# quad_exp_vca_main.net
KiCad netlist of a schematic drawn in EAGLE
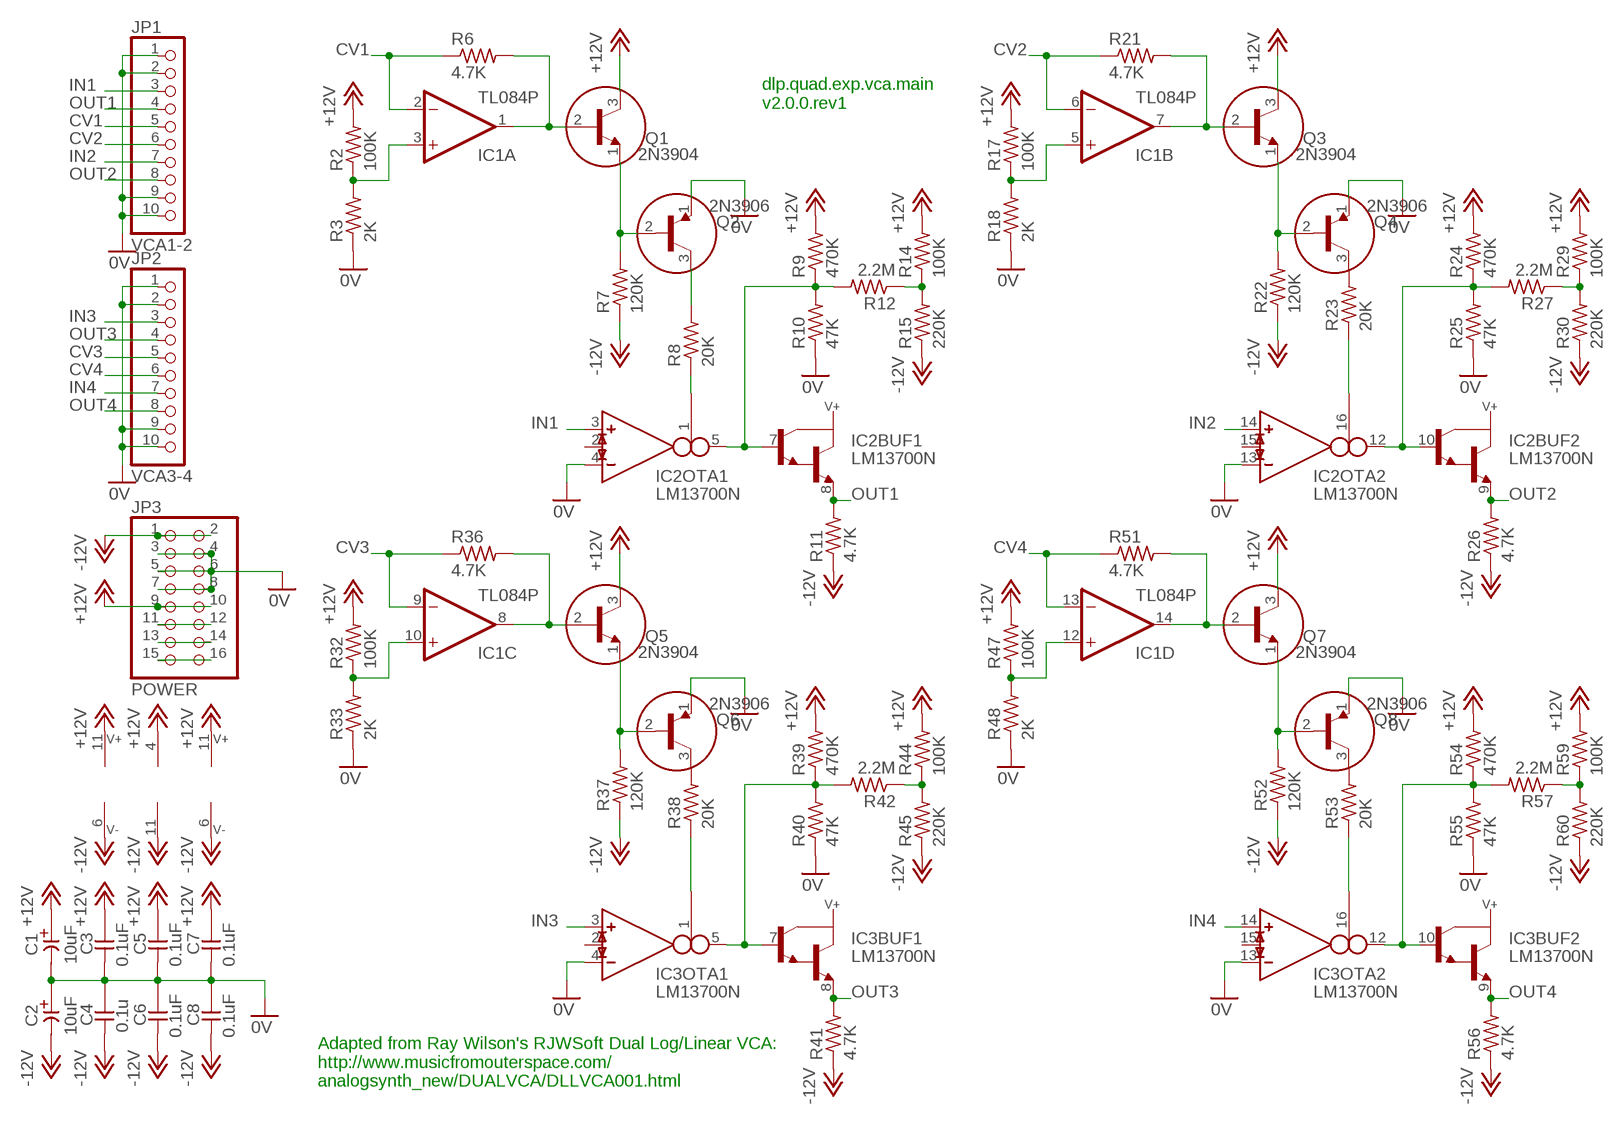
[diagram p0: schematic, sheet 1]

(export (version "E")
  (design (tool "Eeschema 10.0.6"))
  (components
    (comp (ref "C1")
      (value "10uF")
      (footprint "eagle-import:E2-5")
      (libsource (lib "eagle-import") (part "CE-USE2-5"))
    )
    (comp (ref "C2")
      (value "10uF")
      (footprint "eagle-import:E2-5")
      (libsource (lib "eagle-import") (part "CE-USE2-5"))
    )
    (comp (ref "C3")
      (value "0.1uF")
      (footprint "eagle-import:C025-024X044")
      (libsource (lib "eagle-import") (part "CC-US025-024X044"))
    )
    (comp (ref "C4")
      (value "0.1u")
      (footprint "eagle-import:C025-024X044")
      (libsource (lib "eagle-import") (part "CC-US025-024X044"))
    )
    (comp (ref "C5")
      (value "0.1uF")
      (footprint "eagle-import:C025-024X044")
      (libsource (lib "eagle-import") (part "CC-US025-024X044"))
    )
    (comp (ref "C6")
      (value "0.1uF")
      (footprint "eagle-import:C025-024X044")
      (libsource (lib "eagle-import") (part "CC-US025-024X044"))
    )
    (comp (ref "C7")
      (value "0.1uF")
      (footprint "eagle-import:C025-024X044")
      (libsource (lib "eagle-import") (part "CC-US025-024X044"))
    )
    (comp (ref "C8")
      (value "0.1uF")
      (footprint "eagle-import:C025-024X044")
      (libsource (lib "eagle-import") (part "CC-US025-024X044"))
    )
    (comp (ref "IC1")
      (value "TL084P")
      (footprint "eagle-import:DIL14")
      (libsource (lib "eagle-import") (part "TL084P"))
    )
    (comp (ref "IC2")
      (value "LM13700N")
      (footprint "eagle-import:DIL16")
      (libsource (lib "eagle-import") (part "LM13700N"))
    )
    (comp (ref "IC3")
      (value "LM13700N")
      (footprint "eagle-import:DIL16")
      (libsource (lib "eagle-import") (part "LM13700N"))
    )
    (comp (ref "JP1")
      (value "VCA1-2")
      (footprint "eagle-import:1X10")
      (libsource (lib "eagle-import") (part "PINHD-1X10"))
    )
    (comp (ref "JP2")
      (value "VCA3-4")
      (footprint "eagle-import:1X10")
      (libsource (lib "eagle-import") (part "PINHD-1X10"))
    )
    (comp (ref "JP3")
      (value "POWER")
      (footprint "eagle-import:2X08")
      (libsource (lib "eagle-import") (part "PINHD-2X8"))
    )
    (comp (ref "Q1")
      (value "2N3904")
      (footprint "eagle-import:TO92")
      (libsource (lib "eagle-import") (part "2N3904"))
    )
    (comp (ref "Q2")
      (value "2N3906")
      (footprint "eagle-import:TO92")
      (libsource (lib "eagle-import") (part "2N3906"))
    )
    (comp (ref "Q3")
      (value "2N3904")
      (footprint "eagle-import:TO92")
      (libsource (lib "eagle-import") (part "2N3904"))
    )
    (comp (ref "Q4")
      (value "2N3906")
      (footprint "eagle-import:TO92")
      (libsource (lib "eagle-import") (part "2N3906"))
    )
    (comp (ref "Q5")
      (value "2N3904")
      (footprint "eagle-import:TO92")
      (libsource (lib "eagle-import") (part "2N3904"))
    )
    (comp (ref "Q6")
      (value "2N3906")
      (footprint "eagle-import:TO92")
      (libsource (lib "eagle-import") (part "2N3906"))
    )
    (comp (ref "Q7")
      (value "2N3904")
      (footprint "eagle-import:TO92")
      (libsource (lib "eagle-import") (part "2N3904"))
    )
    (comp (ref "Q8")
      (value "2N3906")
      (footprint "eagle-import:TO92")
      (libsource (lib "eagle-import") (part "2N3906"))
    )
    (comp (ref "R2")
      (value "100K")
      (footprint "eagle-import:0207_7")
      (libsource (lib "eagle-import") (part "R-US_0207/7"))
    )
    (comp (ref "R3")
      (value "2K")
      (footprint "eagle-import:0207_7")
      (libsource (lib "eagle-import") (part "R-US_0207/7"))
    )
    (comp (ref "R6")
      (value "4.7K")
      (footprint "eagle-import:0207_7")
      (libsource (lib "eagle-import") (part "R-US_0207/7"))
    )
    (comp (ref "R7")
      (value "120K")
      (footprint "eagle-import:0207_7")
      (libsource (lib "eagle-import") (part "R-US_0207/7"))
    )
    (comp (ref "R8")
      (value "20K")
      (footprint "eagle-import:0207_7")
      (libsource (lib "eagle-import") (part "R-US_0207/7"))
    )
    (comp (ref "R9")
      (value "470K")
      (footprint "eagle-import:0207_7")
      (libsource (lib "eagle-import") (part "R-US_0207/7"))
    )
    (comp (ref "R10")
      (value "47K")
      (footprint "eagle-import:0207_7")
      (libsource (lib "eagle-import") (part "R-US_0207/7"))
    )
    (comp (ref "R11")
      (value "4.7K")
      (footprint "eagle-import:0207_7")
      (libsource (lib "eagle-import") (part "R-US_0207/7"))
    )
    (comp (ref "R12")
      (value "2.2M")
      (footprint "eagle-import:0207_7")
      (libsource (lib "eagle-import") (part "R-US_0207/7"))
    )
    (comp (ref "R14")
      (value "100K")
      (footprint "eagle-import:0207_7")
      (libsource (lib "eagle-import") (part "R-US_0207/7"))
    )
    (comp (ref "R15")
      (value "220K")
      (footprint "eagle-import:0207_7")
      (libsource (lib "eagle-import") (part "R-US_0207/7"))
    )
    (comp (ref "R17")
      (value "100K")
      (footprint "eagle-import:0207_7")
      (libsource (lib "eagle-import") (part "R-US_0207/7"))
    )
    (comp (ref "R18")
      (value "2K")
      (footprint "eagle-import:0207_7")
      (libsource (lib "eagle-import") (part "R-US_0207/7"))
    )
    (comp (ref "R21")
      (value "4.7K")
      (footprint "eagle-import:0207_7")
      (libsource (lib "eagle-import") (part "R-US_0207/7"))
    )
    (comp (ref "R22")
      (value "120K")
      (footprint "eagle-import:0207_7")
      (libsource (lib "eagle-import") (part "R-US_0207/7"))
    )
    (comp (ref "R23")
      (value "20K")
      (footprint "eagle-import:0207_7")
      (libsource (lib "eagle-import") (part "R-US_0207/7"))
    )
    (comp (ref "R24")
      (value "470K")
      (footprint "eagle-import:0207_7")
      (libsource (lib "eagle-import") (part "R-US_0207/7"))
    )
    (comp (ref "R25")
      (value "47K")
      (footprint "eagle-import:0207_7")
      (libsource (lib "eagle-import") (part "R-US_0207/7"))
    )
    (comp (ref "R26")
      (value "4.7K")
      (footprint "eagle-import:0207_7")
      (libsource (lib "eagle-import") (part "R-US_0207/7"))
    )
    (comp (ref "R27")
      (value "2.2M")
      (footprint "eagle-import:0207_7")
      (libsource (lib "eagle-import") (part "R-US_0207/7"))
    )
    (comp (ref "R29")
      (value "100K")
      (footprint "eagle-import:0207_7")
      (libsource (lib "eagle-import") (part "R-US_0207/7"))
    )
    (comp (ref "R30")
      (value "220K")
      (footprint "eagle-import:0207_7")
      (libsource (lib "eagle-import") (part "R-US_0207/7"))
    )
    (comp (ref "R32")
      (value "100K")
      (footprint "eagle-import:0207_7")
      (libsource (lib "eagle-import") (part "R-US_0207/7"))
    )
    (comp (ref "R33")
      (value "2K")
      (footprint "eagle-import:0207_7")
      (libsource (lib "eagle-import") (part "R-US_0207/7"))
    )
    (comp (ref "R36")
      (value "4.7K")
      (footprint "eagle-import:0207_7")
      (libsource (lib "eagle-import") (part "R-US_0207/7"))
    )
    (comp (ref "R37")
      (value "120K")
      (footprint "eagle-import:0207_7")
      (libsource (lib "eagle-import") (part "R-US_0207/7"))
    )
    (comp (ref "R38")
      (value "20K")
      (footprint "eagle-import:0207_7")
      (libsource (lib "eagle-import") (part "R-US_0207/7"))
    )
    (comp (ref "R39")
      (value "470K")
      (footprint "eagle-import:0207_7")
      (libsource (lib "eagle-import") (part "R-US_0207/7"))
    )
    (comp (ref "R40")
      (value "47K")
      (footprint "eagle-import:0207_7")
      (libsource (lib "eagle-import") (part "R-US_0207/7"))
    )
    (comp (ref "R41")
      (value "4.7K")
      (footprint "eagle-import:0207_7")
      (libsource (lib "eagle-import") (part "R-US_0207/7"))
    )
    (comp (ref "R42")
      (value "2.2M")
      (footprint "eagle-import:0207_7")
      (libsource (lib "eagle-import") (part "R-US_0207/7"))
    )
    (comp (ref "R44")
      (value "100K")
      (footprint "eagle-import:0207_7")
      (libsource (lib "eagle-import") (part "R-US_0207/7"))
    )
    (comp (ref "R45")
      (value "220K")
      (footprint "eagle-import:0207_7")
      (libsource (lib "eagle-import") (part "R-US_0207/7"))
    )
    (comp (ref "R47")
      (value "100K")
      (footprint "eagle-import:0207_7")
      (libsource (lib "eagle-import") (part "R-US_0207/7"))
    )
    (comp (ref "R48")
      (value "2K")
      (footprint "eagle-import:0207_7")
      (libsource (lib "eagle-import") (part "R-US_0207/7"))
    )
    (comp (ref "R51")
      (value "4.7K")
      (footprint "eagle-import:0207_7")
      (libsource (lib "eagle-import") (part "R-US_0207/7"))
    )
    (comp (ref "R52")
      (value "120K")
      (footprint "eagle-import:0207_7")
      (libsource (lib "eagle-import") (part "R-US_0207/7"))
    )
    (comp (ref "R53")
      (value "20K")
      (footprint "eagle-import:0207_7")
      (libsource (lib "eagle-import") (part "R-US_0207/7"))
    )
    (comp (ref "R54")
      (value "470K")
      (footprint "eagle-import:0207_7")
      (libsource (lib "eagle-import") (part "R-US_0207/7"))
    )
    (comp (ref "R55")
      (value "47K")
      (footprint "eagle-import:0207_7")
      (libsource (lib "eagle-import") (part "R-US_0207/7"))
    )
    (comp (ref "R56")
      (value "4.7K")
      (footprint "eagle-import:0207_7")
      (libsource (lib "eagle-import") (part "R-US_0207/7"))
    )
    (comp (ref "R57")
      (value "2.2M")
      (footprint "eagle-import:0207_7")
      (libsource (lib "eagle-import") (part "R-US_0207/7"))
    )
    (comp (ref "R59")
      (value "100K")
      (footprint "eagle-import:0207_7")
      (libsource (lib "eagle-import") (part "R-US_0207/7"))
    )
    (comp (ref "R60")
      (value "220K")
      (footprint "eagle-import:0207_7")
      (libsource (lib "eagle-import") (part "R-US_0207/7"))
    )
  )
  (nets
    (net (code "1") (name "+12V") (class "Default")
      (node (ref "C1") (pin "+") (pinfunction "+_+") (pintype "passive"))
      (node (ref "C3") (pin "1") (pinfunction "1_1") (pintype "passive"))
      (node (ref "C5") (pin "1") (pinfunction "1_1") (pintype "passive"))
      (node (ref "C7") (pin "1") (pinfunction "1_1") (pintype "passive"))
      (node (ref "IC1") (pin "4") (pinfunction "V+_4") (pintype "power_in"))
      (node (ref "IC2") (pin "11") (pinfunction "V+_11") (pintype "power_in"))
      (node (ref "IC3") (pin "11") (pinfunction "V+_11") (pintype "power_in"))
      (node (ref "JP3") (pin "10") (pinfunction "10_10") (pintype "passive"))
      (node (ref "JP3") (pin "9") (pinfunction "9_9") (pintype "passive"))
      (node (ref "Q1") (pin "3") (pinfunction "C_3") (pintype "passive"))
      (node (ref "Q3") (pin "3") (pinfunction "C_3") (pintype "passive"))
      (node (ref "Q5") (pin "3") (pinfunction "C_3") (pintype "passive"))
      (node (ref "Q7") (pin "3") (pinfunction "C_3") (pintype "passive"))
      (node (ref "R14") (pin "2") (pinfunction "2_2") (pintype "passive"))
      (node (ref "R17") (pin "2") (pinfunction "2_2") (pintype "passive"))
      (node (ref "R2") (pin "2") (pinfunction "2_2") (pintype "passive"))
      (node (ref "R24") (pin "2") (pinfunction "2_2") (pintype "passive"))
      (node (ref "R29") (pin "2") (pinfunction "2_2") (pintype "passive"))
      (node (ref "R32") (pin "2") (pinfunction "2_2") (pintype "passive"))
      (node (ref "R39") (pin "2") (pinfunction "2_2") (pintype "passive"))
      (node (ref "R44") (pin "2") (pinfunction "2_2") (pintype "passive"))
      (node (ref "R47") (pin "2") (pinfunction "2_2") (pintype "passive"))
      (node (ref "R54") (pin "2") (pinfunction "2_2") (pintype "passive"))
      (node (ref "R59") (pin "2") (pinfunction "2_2") (pintype "passive"))
      (node (ref "R9") (pin "2") (pinfunction "2_2") (pintype "passive"))
    )
    (net (code "2") (name "-12V") (class "Default")
      (node (ref "C2") (pin "-") (pinfunction "-_-") (pintype "passive"))
      (node (ref "C4") (pin "2") (pinfunction "2_2") (pintype "passive"))
      (node (ref "C6") (pin "2") (pinfunction "2_2") (pintype "passive"))
      (node (ref "C8") (pin "2") (pinfunction "2_2") (pintype "passive"))
      (node (ref "IC1") (pin "11") (pinfunction "V-_11") (pintype "power_in"))
      (node (ref "IC2") (pin "6") (pinfunction "V-_6") (pintype "power_in"))
      (node (ref "IC3") (pin "6") (pinfunction "V-_6") (pintype "power_in"))
      (node (ref "JP3") (pin "1") (pinfunction "1_1") (pintype "passive"))
      (node (ref "JP3") (pin "2") (pinfunction "2_2") (pintype "passive"))
      (node (ref "R11") (pin "1") (pinfunction "1_1") (pintype "passive"))
      (node (ref "R15") (pin "1") (pinfunction "1_1") (pintype "passive"))
      (node (ref "R22") (pin "1") (pinfunction "1_1") (pintype "passive"))
      (node (ref "R26") (pin "1") (pinfunction "1_1") (pintype "passive"))
      (node (ref "R30") (pin "1") (pinfunction "1_1") (pintype "passive"))
      (node (ref "R37") (pin "1") (pinfunction "1_1") (pintype "passive"))
      (node (ref "R41") (pin "1") (pinfunction "1_1") (pintype "passive"))
      (node (ref "R45") (pin "1") (pinfunction "1_1") (pintype "passive"))
      (node (ref "R52") (pin "1") (pinfunction "1_1") (pintype "passive"))
      (node (ref "R56") (pin "1") (pinfunction "1_1") (pintype "passive"))
      (node (ref "R60") (pin "1") (pinfunction "1_1") (pintype "passive"))
      (node (ref "R7") (pin "1") (pinfunction "1_1") (pintype "passive"))
    )
    (net (code "3") (name "/CV1") (class "Default")
      (node (ref "IC1") (pin "2") (pinfunction "-IN_2") (pintype "input"))
      (node (ref "JP1") (pin "5") (pinfunction "5_5") (pintype "passive"))
      (node (ref "R6") (pin "1") (pinfunction "1_1") (pintype "passive"))
    )
    (net (code "4") (name "/CV2") (class "Default")
      (node (ref "IC1") (pin "6") (pinfunction "-IN_6") (pintype "input"))
      (node (ref "JP1") (pin "6") (pinfunction "6_6") (pintype "passive"))
      (node (ref "R21") (pin "1") (pinfunction "1_1") (pintype "passive"))
    )
    (net (code "5") (name "/CV3") (class "Default")
      (node (ref "IC1") (pin "9") (pinfunction "-IN_9") (pintype "input"))
      (node (ref "JP2") (pin "5") (pinfunction "5_5") (pintype "passive"))
      (node (ref "R36") (pin "1") (pinfunction "1_1") (pintype "passive"))
    )
    (net (code "6") (name "/CV4") (class "Default")
      (node (ref "IC1") (pin "13") (pinfunction "-IN_13") (pintype "input"))
      (node (ref "JP2") (pin "6") (pinfunction "6_6") (pintype "passive"))
      (node (ref "R51") (pin "1") (pinfunction "1_1") (pintype "passive"))
    )
    (net (code "7") (name "/IN1") (class "Default")
      (node (ref "IC2") (pin "3") (pinfunction "IN_P_3") (pintype "input"))
      (node (ref "JP1") (pin "3") (pinfunction "3_3") (pintype "passive"))
    )
    (net (code "8") (name "/IN2") (class "Default")
      (node (ref "IC2") (pin "14") (pinfunction "IN_P_14") (pintype "input"))
      (node (ref "JP1") (pin "7") (pinfunction "7_7") (pintype "passive"))
    )
    (net (code "9") (name "/IN3") (class "Default")
      (node (ref "IC3") (pin "3") (pinfunction "IN_P_3") (pintype "input"))
      (node (ref "JP2") (pin "3") (pinfunction "3_3") (pintype "passive"))
    )
    (net (code "10") (name "/IN4") (class "Default")
      (node (ref "IC3") (pin "14") (pinfunction "IN_P_14") (pintype "input"))
      (node (ref "JP2") (pin "7") (pinfunction "7_7") (pintype "passive"))
    )
    (net (code "11") (name "/OUT1") (class "Default")
      (node (ref "IC2") (pin "8") (pinfunction "E_8") (pintype "passive"))
      (node (ref "JP1") (pin "4") (pinfunction "4_4") (pintype "passive"))
      (node (ref "R11") (pin "2") (pinfunction "2_2") (pintype "passive"))
    )
    (net (code "12") (name "/OUT2") (class "Default")
      (node (ref "IC2") (pin "9") (pinfunction "E_9") (pintype "passive"))
      (node (ref "JP1") (pin "8") (pinfunction "8_8") (pintype "passive"))
      (node (ref "R26") (pin "2") (pinfunction "2_2") (pintype "passive"))
    )
    (net (code "13") (name "/OUT3") (class "Default")
      (node (ref "IC3") (pin "8") (pinfunction "E_8") (pintype "passive"))
      (node (ref "JP2") (pin "4") (pinfunction "4_4") (pintype "passive"))
      (node (ref "R41") (pin "2") (pinfunction "2_2") (pintype "passive"))
    )
    (net (code "14") (name "/OUT4") (class "Default")
      (node (ref "IC3") (pin "9") (pinfunction "E_9") (pintype "passive"))
      (node (ref "JP2") (pin "8") (pinfunction "8_8") (pintype "passive"))
      (node (ref "R56") (pin "2") (pinfunction "2_2") (pintype "passive"))
    )
    (net (code "15") (name "0V") (class "Default")
      (node (ref "C1") (pin "-") (pinfunction "-_-") (pintype "passive"))
      (node (ref "C2") (pin "+") (pinfunction "+_+") (pintype "passive"))
      (node (ref "C3") (pin "2") (pinfunction "2_2") (pintype "passive"))
      (node (ref "C4") (pin "1") (pinfunction "1_1") (pintype "passive"))
      (node (ref "C5") (pin "2") (pinfunction "2_2") (pintype "passive"))
      (node (ref "C6") (pin "1") (pinfunction "1_1") (pintype "passive"))
      (node (ref "C7") (pin "2") (pinfunction "2_2") (pintype "passive"))
      (node (ref "C8") (pin "1") (pinfunction "1_1") (pintype "passive"))
      (node (ref "IC2") (pin "13") (pinfunction "IN_N_13") (pintype "input"))
      (node (ref "IC2") (pin "4") (pinfunction "IN_N_4") (pintype "input"))
      (node (ref "IC3") (pin "13") (pinfunction "IN_N_13") (pintype "input"))
      (node (ref "IC3") (pin "4") (pinfunction "IN_N_4") (pintype "input"))
      (node (ref "JP1") (pin "1") (pinfunction "1_1") (pintype "passive"))
      (node (ref "JP1") (pin "10") (pinfunction "10_10") (pintype "passive"))
      (node (ref "JP1") (pin "2") (pinfunction "2_2") (pintype "passive"))
      (node (ref "JP1") (pin "9") (pinfunction "9_9") (pintype "passive"))
      (node (ref "JP2") (pin "1") (pinfunction "1_1") (pintype "passive"))
      (node (ref "JP2") (pin "10") (pinfunction "10_10") (pintype "passive"))
      (node (ref "JP2") (pin "2") (pinfunction "2_2") (pintype "passive"))
      (node (ref "JP2") (pin "9") (pinfunction "9_9") (pintype "passive"))
      (node (ref "JP3") (pin "3") (pinfunction "3_3") (pintype "passive"))
      (node (ref "JP3") (pin "4") (pinfunction "4_4") (pintype "passive"))
      (node (ref "JP3") (pin "5") (pinfunction "5_5") (pintype "passive"))
      (node (ref "JP3") (pin "6") (pinfunction "6_6") (pintype "passive"))
      (node (ref "JP3") (pin "7") (pinfunction "7_7") (pintype "passive"))
      (node (ref "JP3") (pin "8") (pinfunction "8_8") (pintype "passive"))
      (node (ref "Q2") (pin "1") (pinfunction "E_1") (pintype "passive"))
      (node (ref "Q4") (pin "1") (pinfunction "E_1") (pintype "passive"))
      (node (ref "Q6") (pin "1") (pinfunction "E_1") (pintype "passive"))
      (node (ref "Q8") (pin "1") (pinfunction "E_1") (pintype "passive"))
      (node (ref "R10") (pin "1") (pinfunction "1_1") (pintype "passive"))
      (node (ref "R18") (pin "1") (pinfunction "1_1") (pintype "passive"))
      (node (ref "R25") (pin "1") (pinfunction "1_1") (pintype "passive"))
      (node (ref "R3") (pin "1") (pinfunction "1_1") (pintype "passive"))
      (node (ref "R33") (pin "1") (pinfunction "1_1") (pintype "passive"))
      (node (ref "R40") (pin "1") (pinfunction "1_1") (pintype "passive"))
      (node (ref "R48") (pin "1") (pinfunction "1_1") (pintype "passive"))
      (node (ref "R55") (pin "1") (pinfunction "1_1") (pintype "passive"))
    )
    (net (code "16") (name "Net-(IC1A-+IN)") (class "Default")
      (node (ref "IC1") (pin "3") (pinfunction "+IN_3") (pintype "input"))
      (node (ref "R2") (pin "1") (pinfunction "1_1") (pintype "passive"))
      (node (ref "R3") (pin "2") (pinfunction "2_2") (pintype "passive"))
    )
    (net (code "17") (name "Net-(IC1A-OUT)") (class "Default")
      (node (ref "IC1") (pin "1") (pinfunction "OUT_1") (pintype "output"))
      (node (ref "Q1") (pin "2") (pinfunction "B_2") (pintype "passive"))
      (node (ref "R6") (pin "2") (pinfunction "2_2") (pintype "passive"))
    )
    (net (code "18") (name "Net-(IC1B-+IN)") (class "Default")
      (node (ref "IC1") (pin "5") (pinfunction "+IN_5") (pintype "input"))
      (node (ref "R17") (pin "1") (pinfunction "1_1") (pintype "passive"))
      (node (ref "R18") (pin "2") (pinfunction "2_2") (pintype "passive"))
    )
    (net (code "19") (name "Net-(IC1B-OUT)") (class "Default")
      (node (ref "IC1") (pin "7") (pinfunction "OUT_7") (pintype "output"))
      (node (ref "Q3") (pin "2") (pinfunction "B_2") (pintype "passive"))
      (node (ref "R21") (pin "2") (pinfunction "2_2") (pintype "passive"))
    )
    (net (code "20") (name "Net-(IC1C-+IN)") (class "Default")
      (node (ref "IC1") (pin "10") (pinfunction "+IN_10") (pintype "input"))
      (node (ref "R32") (pin "1") (pinfunction "1_1") (pintype "passive"))
      (node (ref "R33") (pin "2") (pinfunction "2_2") (pintype "passive"))
    )
    (net (code "21") (name "Net-(IC1C-OUT)") (class "Default")
      (node (ref "IC1") (pin "8") (pinfunction "OUT_8") (pintype "output"))
      (node (ref "Q5") (pin "2") (pinfunction "B_2") (pintype "passive"))
      (node (ref "R36") (pin "2") (pinfunction "2_2") (pintype "passive"))
    )
    (net (code "22") (name "Net-(IC1D-+IN)") (class "Default")
      (node (ref "IC1") (pin "12") (pinfunction "+IN_12") (pintype "input"))
      (node (ref "R47") (pin "1") (pinfunction "1_1") (pintype "passive"))
      (node (ref "R48") (pin "2") (pinfunction "2_2") (pintype "passive"))
    )
    (net (code "23") (name "Net-(IC1D-OUT)") (class "Default")
      (node (ref "IC1") (pin "14") (pinfunction "OUT_14") (pintype "output"))
      (node (ref "Q7") (pin "2") (pinfunction "B_2") (pintype "passive"))
      (node (ref "R51") (pin "2") (pinfunction "2_2") (pintype "passive"))
    )
    (net (code "24") (name "Net-(IC2A-B)") (class "Default")
      (node (ref "IC2") (pin "5") (pinfunction "OUT_5") (pintype "output"))
      (node (ref "IC2") (pin "7") (pinfunction "B_7") (pintype "passive"))
      (node (ref "R10") (pin "2") (pinfunction "2_2") (pintype "passive"))
      (node (ref "R12") (pin "2") (pinfunction "2_2") (pintype "passive"))
      (node (ref "R9") (pin "1") (pinfunction "1_1") (pintype "passive"))
    )
    (net (code "25") (name "Net-(IC2B-B)") (class "Default")
      (node (ref "IC2") (pin "10") (pinfunction "B_10") (pintype "passive"))
      (node (ref "IC2") (pin "12") (pinfunction "OUT_12") (pintype "output"))
      (node (ref "R24") (pin "1") (pinfunction "1_1") (pintype "passive"))
      (node (ref "R25") (pin "2") (pinfunction "2_2") (pintype "passive"))
      (node (ref "R27") (pin "2") (pinfunction "2_2") (pintype "passive"))
    )
    (net (code "26") (name "Net-(IC2C-I_BIAS)") (class "Default")
      (node (ref "IC2") (pin "1") (pinfunction "I_BIAS_1") (pintype "input"))
      (node (ref "R8") (pin "1") (pinfunction "1_1") (pintype "passive"))
    )
    (net (code "27") (name "Net-(IC2D-I_BIAS)") (class "Default")
      (node (ref "IC2") (pin "16") (pinfunction "I_BIAS_16") (pintype "input"))
      (node (ref "R23") (pin "1") (pinfunction "1_1") (pintype "passive"))
    )
    (net (code "28") (name "Net-(IC3A-B)") (class "Default")
      (node (ref "IC3") (pin "5") (pinfunction "OUT_5") (pintype "output"))
      (node (ref "IC3") (pin "7") (pinfunction "B_7") (pintype "passive"))
      (node (ref "R39") (pin "1") (pinfunction "1_1") (pintype "passive"))
      (node (ref "R40") (pin "2") (pinfunction "2_2") (pintype "passive"))
      (node (ref "R42") (pin "2") (pinfunction "2_2") (pintype "passive"))
    )
    (net (code "29") (name "Net-(IC3B-B)") (class "Default")
      (node (ref "IC3") (pin "10") (pinfunction "B_10") (pintype "passive"))
      (node (ref "IC3") (pin "12") (pinfunction "OUT_12") (pintype "output"))
      (node (ref "R54") (pin "1") (pinfunction "1_1") (pintype "passive"))
      (node (ref "R55") (pin "2") (pinfunction "2_2") (pintype "passive"))
      (node (ref "R57") (pin "2") (pinfunction "2_2") (pintype "passive"))
    )
    (net (code "30") (name "Net-(IC3C-I_BIAS)") (class "Default")
      (node (ref "IC3") (pin "1") (pinfunction "I_BIAS_1") (pintype "input"))
      (node (ref "R38") (pin "1") (pinfunction "1_1") (pintype "passive"))
    )
    (net (code "31") (name "Net-(IC3D-I_BIAS)") (class "Default")
      (node (ref "IC3") (pin "16") (pinfunction "I_BIAS_16") (pintype "input"))
      (node (ref "R53") (pin "1") (pinfunction "1_1") (pintype "passive"))
    )
    (net (code "32") (name "Net-(JP3-Pad11)") (class "Default")
      (node (ref "JP3") (pin "11") (pinfunction "11_11") (pintype "passive"))
      (node (ref "JP3") (pin "12") (pinfunction "12_12") (pintype "passive"))
    )
    (net (code "33") (name "Net-(JP3-Pad13)") (class "Default")
      (node (ref "JP3") (pin "13") (pinfunction "13_13") (pintype "passive"))
      (node (ref "JP3") (pin "14") (pinfunction "14_14") (pintype "passive"))
    )
    (net (code "34") (name "Net-(JP3-Pad15)") (class "Default")
      (node (ref "JP3") (pin "15") (pinfunction "15_15") (pintype "passive"))
      (node (ref "JP3") (pin "16") (pinfunction "16_16") (pintype "passive"))
    )
    (net (code "35") (name "Net-(Q1-E)") (class "Default")
      (node (ref "Q1") (pin "1") (pinfunction "E_1") (pintype "passive"))
      (node (ref "Q2") (pin "2") (pinfunction "B_2") (pintype "passive"))
      (node (ref "R7") (pin "2") (pinfunction "2_2") (pintype "passive"))
    )
    (net (code "36") (name "Net-(Q2-C)") (class "Default")
      (node (ref "Q2") (pin "3") (pinfunction "C_3") (pintype "passive"))
      (node (ref "R8") (pin "2") (pinfunction "2_2") (pintype "passive"))
    )
    (net (code "37") (name "Net-(Q3-E)") (class "Default")
      (node (ref "Q3") (pin "1") (pinfunction "E_1") (pintype "passive"))
      (node (ref "Q4") (pin "2") (pinfunction "B_2") (pintype "passive"))
      (node (ref "R22") (pin "2") (pinfunction "2_2") (pintype "passive"))
    )
    (net (code "38") (name "Net-(Q4-C)") (class "Default")
      (node (ref "Q4") (pin "3") (pinfunction "C_3") (pintype "passive"))
      (node (ref "R23") (pin "2") (pinfunction "2_2") (pintype "passive"))
    )
    (net (code "39") (name "Net-(Q5-E)") (class "Default")
      (node (ref "Q5") (pin "1") (pinfunction "E_1") (pintype "passive"))
      (node (ref "Q6") (pin "2") (pinfunction "B_2") (pintype "passive"))
      (node (ref "R37") (pin "2") (pinfunction "2_2") (pintype "passive"))
    )
    (net (code "40") (name "Net-(Q6-C)") (class "Default")
      (node (ref "Q6") (pin "3") (pinfunction "C_3") (pintype "passive"))
      (node (ref "R38") (pin "2") (pinfunction "2_2") (pintype "passive"))
    )
    (net (code "41") (name "Net-(Q7-E)") (class "Default")
      (node (ref "Q7") (pin "1") (pinfunction "E_1") (pintype "passive"))
      (node (ref "Q8") (pin "2") (pinfunction "B_2") (pintype "passive"))
      (node (ref "R52") (pin "2") (pinfunction "2_2") (pintype "passive"))
    )
    (net (code "42") (name "Net-(Q8-C)") (class "Default")
      (node (ref "Q8") (pin "3") (pinfunction "C_3") (pintype "passive"))
      (node (ref "R53") (pin "2") (pinfunction "2_2") (pintype "passive"))
    )
    (net (code "43") (name "Net-(R12-Pad1)") (class "Default")
      (node (ref "R12") (pin "1") (pinfunction "1_1") (pintype "passive"))
      (node (ref "R14") (pin "1") (pinfunction "1_1") (pintype "passive"))
      (node (ref "R15") (pin "2") (pinfunction "2_2") (pintype "passive"))
    )
    (net (code "44") (name "Net-(R27-Pad1)") (class "Default")
      (node (ref "R27") (pin "1") (pinfunction "1_1") (pintype "passive"))
      (node (ref "R29") (pin "1") (pinfunction "1_1") (pintype "passive"))
      (node (ref "R30") (pin "2") (pinfunction "2_2") (pintype "passive"))
    )
    (net (code "45") (name "Net-(R42-Pad1)") (class "Default")
      (node (ref "R42") (pin "1") (pinfunction "1_1") (pintype "passive"))
      (node (ref "R44") (pin "1") (pinfunction "1_1") (pintype "passive"))
      (node (ref "R45") (pin "2") (pinfunction "2_2") (pintype "passive"))
    )
    (net (code "46") (name "Net-(R57-Pad1)") (class "Default")
      (node (ref "R57") (pin "1") (pinfunction "1_1") (pintype "passive"))
      (node (ref "R59") (pin "1") (pinfunction "1_1") (pintype "passive"))
      (node (ref "R60") (pin "2") (pinfunction "2_2") (pintype "passive"))
    )
    (net (code "47") (name "unconnected-(IC2C-I_DIODE-Pad2)") (class "Default")
      (node (ref "IC2") (pin "2") (pinfunction "I_DIODE_2") (pintype "input"))
    )
    (net (code "48") (name "unconnected-(IC2D-I_DIODE-Pad15)") (class "Default")
      (node (ref "IC2") (pin "15") (pinfunction "I_DIODE_15") (pintype "input"))
    )
    (net (code "49") (name "unconnected-(IC3C-I_DIODE-Pad2)") (class "Default")
      (node (ref "IC3") (pin "2") (pinfunction "I_DIODE_2") (pintype "input"))
    )
    (net (code "50") (name "unconnected-(IC3D-I_DIODE-Pad15)") (class "Default")
      (node (ref "IC3") (pin "15") (pinfunction "I_DIODE_15") (pintype "input"))
    )
  )
)
